# Battery.net
KiCad netlist of a schematic drawn in Altium Designer
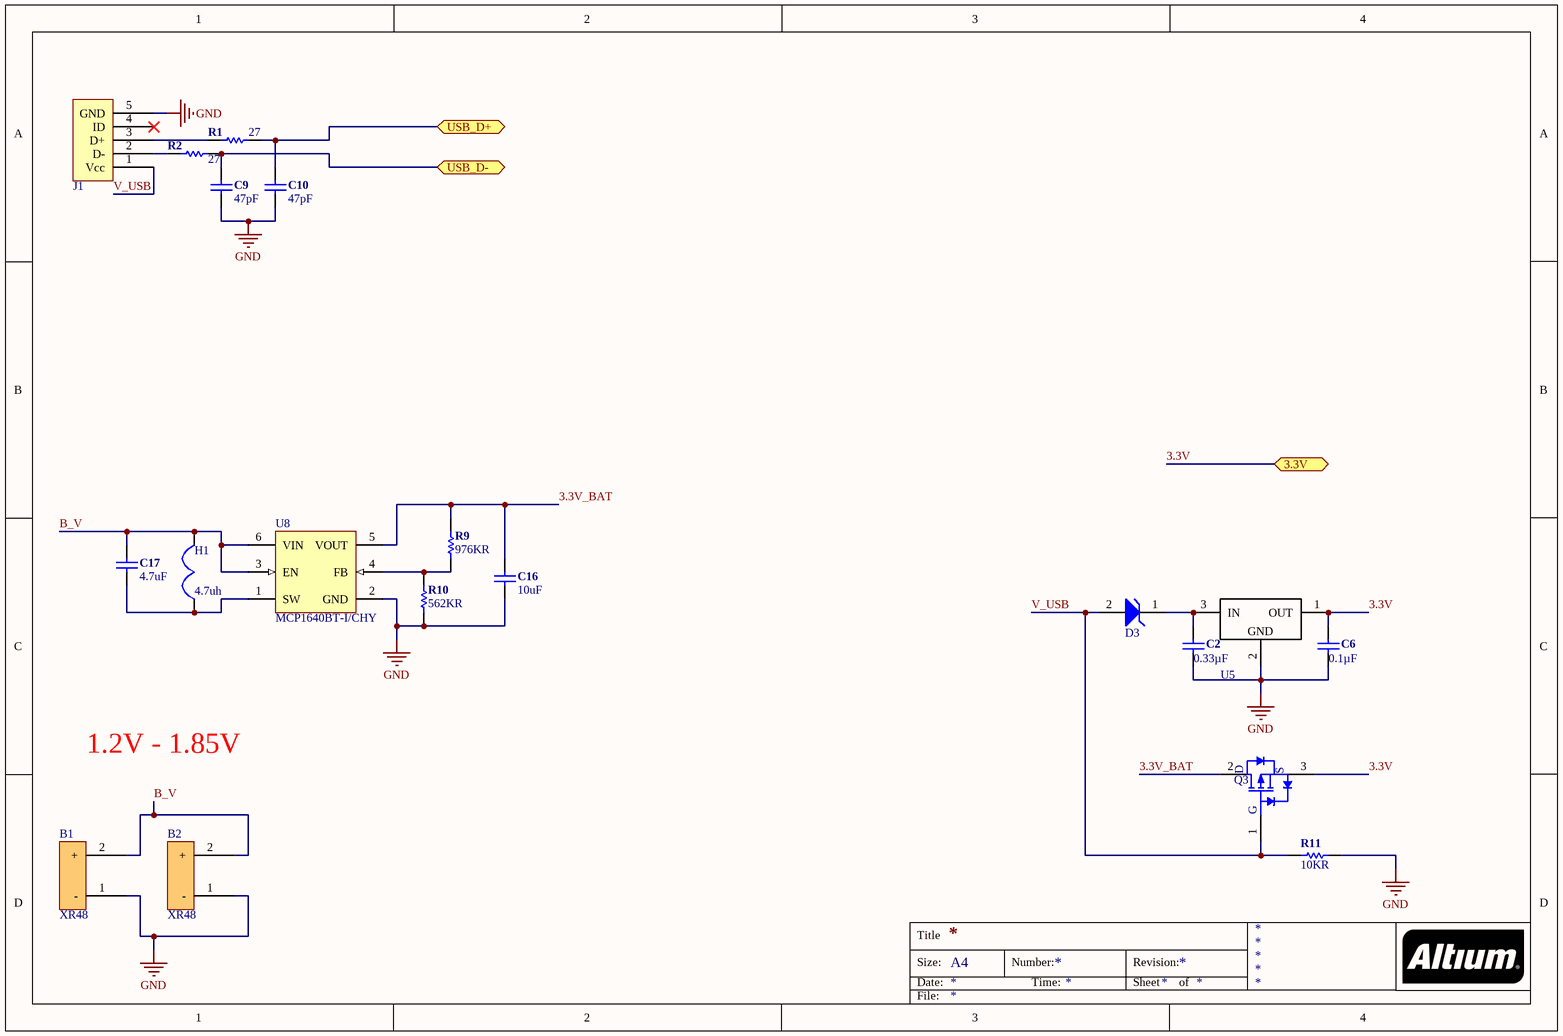
[diagram p0: Battery.SchDoc]

(export (version "E")
  (design (tool "Eeschema 10.0.6"))
  (components
    (comp (ref "B1")
      (value "XR48")
      (footprint "XR48")
      (description "RETAINER COIN CELL 7.9MM SMD")
      (fields
        (field (name "MANUFACTURER") "Keystone Electronics")
        (field (name "MANUFACTURER PART NUMBER") "2988")
      )
      (libsource (lib "Glove") (part "XR48"))
    )
    (comp (ref "B2")
      (value "XR48")
      (footprint "XR48")
      (description "RETAINER COIN CELL 7.9MM SMD")
      (fields
        (field (name "MANUFACTURER") "Keystone Electronics")
        (field (name "MANUFACTURER PART NUMBER") "2988")
      )
      (libsource (lib "Glove") (part "XR48"))
    )
    (comp (ref "C2")
      (value "0.33µF")
      (footprint "CAP-0805(2012)-R")
      (description "___ OHM ___ mW 0805(2012) SMD")
      (fields
        (field (name "MANUFACTURER") "Yageo")
        (field (name "MANUFACTURER PART NUMBER") "CC0805KKX7R7BB334")
      )
      (libsource (lib "Glove") (part "C-0805(2012)"))
    )
    (comp (ref "C6")
      (value "0.1µF")
      (footprint "CAP-0805(2012)-R")
      (description "___ OHM ___ mW 0805(2012) SMD")
      (fields
        (field (name "MANUFACTURER") "Yageo")
        (field (name "MANUFACTURER PART NUMBER") "CC0805KRX7R9BB104")
      )
      (libsource (lib "Glove") (part "C-0805(2012)"))
    )
    (comp (ref "C9")
      (value "47pF")
      (footprint "CAP-0805(2012)-R")
      (description "___ OHM ___ mW 0805(2012) SMD")
      (fields
        (field (name "MANUFACTURER") "Yageo")
        (field (name "MANUFACTURER PART NUMBER") "CC0805JRNPO9BN470")
      )
      (libsource (lib "Glove") (part "C-0805(2012)"))
    )
    (comp (ref "C10")
      (value "47pF")
      (footprint "CAP-0805(2012)-R")
      (description "___ OHM ___ mW 0805(2012) SMD")
      (fields
        (field (name "MANUFACTURER") "Yageo")
        (field (name "MANUFACTURER PART NUMBER") "CC0805JRNPO9BN470")
      )
      (libsource (lib "Glove") (part "C-0805(2012)"))
    )
    (comp (ref "C16")
      (value "10uF")
      (footprint "CAP-0805(2012)-R")
      (description "___ OHM ___ mW 0805(2012) SMD")
      (fields
        (field (name "MANUFACTURER") "Murata")
        (field (name "MANUFACTURER PART NUMBER") "GRM219R61A106KE44D")
      )
      (libsource (lib "Glove") (part "C-0805(2012)"))
    )
    (comp (ref "C17")
      (value "4.7uF")
      (footprint "CAP-0805(2012)-R")
      (description "___ OHM ___ mW 0805(2012) SMD")
      (fields
        (field (name "MANUFACTURER") "Murata")
        (field (name "MANUFACTURER PART NUMBER") "GRM21BR61C475KA88L")
      )
      (libsource (lib "Glove") (part "C-0805(2012)"))
    )
    (comp (ref "D3")
      (value "Shottky_Diode")
      (footprint "SOD-323-2")
      (description "BAT60AE6327HTSA1")
      (fields (field (name "MANUFACTURER") "Infineon"))
      (libsource (lib "Glove") (part "Shottky_Diode"))
    )
    (comp (ref "H1")
      (value "H-0805(2012)")
      (footprint "H-0805(2012)-H")
      (fields
        (field (name "MANUFACTURER") "TDK")
        (field (name "MANUFACTURER PART NUMBER") "MLP2012S4R7MT0S1")
        (field (name "TOLERANCE") "20%")
        (field (name "INDUCTANCE") "4.7uh")
      )
      (libsource (lib "Glove") (part "H-0805(2012)"))
    )
    (comp (ref "J1")
      (value "USB")
      (footprint "USB_Connector_5P_MICRO_USB_FCI")
      (description "USB_Connector_5P_MICRO_USB_FCI")
      (fields
        (field (name "MANUFACTURER") "Amphenol FCI")
        (field (name "MANUFACTURER PART NUMBER") "10118194-0001LF")
      )
      (libsource (lib "Glove") (part "USB"))
    )
    (comp (ref "Q3")
      (value "DMP1045U")
      (footprint "SOT23-3")
      (fields (field (name "MANUFACTURER") "Diodes") (field (name "MANUFACTURER PART NUMBER") "DMP1045U-7"))
      (libsource (lib "Glove") (part "DMP1045U"))
    )
    (comp (ref "R1")
      (value "27")
      (footprint "R-0805(2012)-R")
      (description "___ OHM ___ mW 0805(2012) SMD")
      (fields
        (field (name "MANUFACTURER") "Yageo")
        (field (name "MANUFACTURER PART NUMBER") "RC0805JR-0727RL")
      )
      (libsource (lib "Glove") (part "R-0805(2012)"))
    )
    (comp (ref "R2")
      (value "27")
      (footprint "R-0805(2012)-R")
      (description "___ OHM ___ mW 0805(2012) SMD")
      (fields
        (field (name "MANUFACTURER") "Yageo")
        (field (name "MANUFACTURER PART NUMBER") "RC0805JR-0727RL")
      )
      (libsource (lib "Glove") (part "R-0805(2012)"))
    )
    (comp (ref "R9")
      (value "976KR")
      (footprint "R-0805(2012)-R")
      (description "___ OHM ___ mW 0805(2012) SMD")
      (fields
        (field (name "MANUFACTURER") "Panasonic ECG")
        (field (name "MANUFACTURER PART NUMBER") "ERJ-6ENF9763V")
      )
      (libsource (lib "Glove") (part "R-0805(2012)"))
    )
    (comp (ref "R10")
      (value "562KR")
      (footprint "R-0805(2012)-R")
      (description "___ OHM ___ mW 0805(2012) SMD")
      (fields
        (field (name "MANUFACTURER") "Vishay")
        (field (name "MANUFACTURER PART NUMBER") "CRCW0805562KFKEA")
      )
      (libsource (lib "Glove") (part "R-0805(2012)"))
    )
    (comp (ref "R11")
      (value "10KR")
      (footprint "R-0805(2012)-R")
      (description "___ OHM ___ mW 0805(2012) SMD")
      (fields
        (field (name "MANUFACTURER") "Yageo")
        (field (name "MANUFACTURER PART NUMBER") "RC0805FR-0710KL")
      )
      (libsource (lib "Glove") (part "R-0805(2012)"))
    )
    (comp (ref "U5")
      (value "L78L33ACUTR")
      (footprint "SOT89-3")
      (fields (field (name "MANUFACTURER") "STMicroelectronics"))
      (libsource (lib "Glove") (part "L78L33ACUTR"))
    )
    (comp (ref "U8")
      (value "MCP1640BT-I/CHY")
      (footprint "MCHP-SOT-23-CHY6_L")
      (fields (field (name "MANUFACTURER") "Microchip"))
      (libsource (lib "Altium Content Vault") (part "CMP-0139-00285-1"))
    )
  )
  (nets
    (net (code "1") (name "/3.3V") (class "Default")
      (node (ref "C6") (pin "1") (pinfunction "1_1") (pintype "passive"))
      (node (ref "Q3") (pin "3") (pinfunction "S_3") (pintype "passive"))
      (node (ref "U5") (pin "1") (pinfunction "OUT_1") (pintype "power_in"))
    )
    (net (code "2") (name "/3.3V_BAT") (class "Default")
      (node (ref "C16") (pin "1") (pinfunction "1_1") (pintype "passive"))
      (node (ref "Q3") (pin "2") (pinfunction "D_2") (pintype "passive"))
      (node (ref "R9") (pin "1") (pinfunction "1_1") (pintype "passive"))
      (node (ref "U8") (pin "5") (pinfunction "VOUT_5") (pintype "power_in"))
    )
    (net (code "3") (name "/B_V") (class "Default")
      (node (ref "B1") (pin "2") (pinfunction "+_2") (pintype "passive"))
      (node (ref "B2") (pin "2") (pinfunction "+_2") (pintype "passive"))
      (node (ref "C17") (pin "1") (pinfunction "1_1") (pintype "passive"))
      (node (ref "H1") (pin "2") (pinfunction "2_2") (pintype "passive"))
      (node (ref "U8") (pin "3") (pinfunction "EN_3") (pintype "input"))
      (node (ref "U8") (pin "6") (pinfunction "VIN_6") (pintype "power_in"))
    )
    (net (code "4") (name "/USB_D+") (class "Default")
      (node (ref "C10") (pin "2") (pinfunction "2_2") (pintype "passive"))
      (node (ref "R1") (pin "2") (pinfunction "2_2") (pintype "passive"))
    )
    (net (code "5") (name "/USB_D-") (class "Default")
      (node (ref "C9") (pin "2") (pinfunction "2_2") (pintype "passive"))
      (node (ref "R2") (pin "2") (pinfunction "2_2") (pintype "passive"))
    )
    (net (code "6") (name "/V_USB") (class "Default")
      (node (ref "D3") (pin "2") (pinfunction "A_2") (pintype "passive"))
      (node (ref "J1") (pin "1") (pinfunction "Vcc_1") (pintype "passive"))
      (node (ref "Q3") (pin "1") (pinfunction "G_1") (pintype "passive"))
      (node (ref "R11") (pin "2") (pinfunction "2_2") (pintype "passive"))
    )
    (net (code "7") (name "GND") (class "Default")
      (node (ref "B1") (pin "1") (pinfunction "-_1") (pintype "passive"))
      (node (ref "B2") (pin "1") (pinfunction "-_1") (pintype "passive"))
      (node (ref "C10") (pin "1") (pinfunction "1_1") (pintype "passive"))
      (node (ref "C16") (pin "2") (pinfunction "2_2") (pintype "passive"))
      (node (ref "C2") (pin "2") (pinfunction "2_2") (pintype "passive"))
      (node (ref "C6") (pin "2") (pinfunction "2_2") (pintype "passive"))
      (node (ref "C9") (pin "1") (pinfunction "1_1") (pintype "passive"))
      (node (ref "J1") (pin "5") (pinfunction "GND_5") (pintype "passive"))
      (node (ref "R10") (pin "2") (pinfunction "2_2") (pintype "passive"))
      (node (ref "R11") (pin "1") (pinfunction "1_1") (pintype "passive"))
      (node (ref "U5") (pin "2") (pinfunction "GND_2") (pintype "power_in"))
      (node (ref "U8") (pin "2") (pinfunction "GND_2") (pintype "power_in"))
    )
    (net (code "8") (name "Net-(D3-K)") (class "Default")
      (node (ref "C2") (pin "1") (pinfunction "1_1") (pintype "passive"))
      (node (ref "D3") (pin "1") (pinfunction "K_1") (pintype "passive"))
      (node (ref "U5") (pin "3") (pinfunction "IN_3") (pintype "passive"))
    )
    (net (code "9") (name "Net-(J1-D+)") (class "Default")
      (node (ref "J1") (pin "3") (pinfunction "D+_3") (pintype "passive"))
      (node (ref "R1") (pin "1") (pinfunction "1_1") (pintype "passive"))
    )
    (net (code "10") (name "Net-(J1-D-)") (class "Default")
      (node (ref "J1") (pin "2") (pinfunction "D-_2") (pintype "passive"))
      (node (ref "R2") (pin "1") (pinfunction "1_1") (pintype "passive"))
    )
    (net (code "11") (name "Net-(U8-FB)") (class "Default")
      (node (ref "R10") (pin "1") (pinfunction "1_1") (pintype "passive"))
      (node (ref "R9") (pin "2") (pinfunction "2_2") (pintype "passive"))
      (node (ref "U8") (pin "4") (pinfunction "FB_4") (pintype "input"))
    )
    (net (code "12") (name "Net-(U8-SW)") (class "Default")
      (node (ref "C17") (pin "2") (pinfunction "2_2") (pintype "passive"))
      (node (ref "H1") (pin "1") (pinfunction "1_1") (pintype "passive"))
      (node (ref "U8") (pin "1") (pinfunction "SW_1") (pintype "power_in"))
    )
    (net (code "13") (name "unconnected-(J1-ID-Pad4)") (class "Default")
      (node (ref "J1") (pin "4") (pinfunction "ID_4") (pintype "passive+no_connect"))
    )
  )
)
